# Fan_Relay.net
KiCad netlist of a schematic drawn in Altium Designer
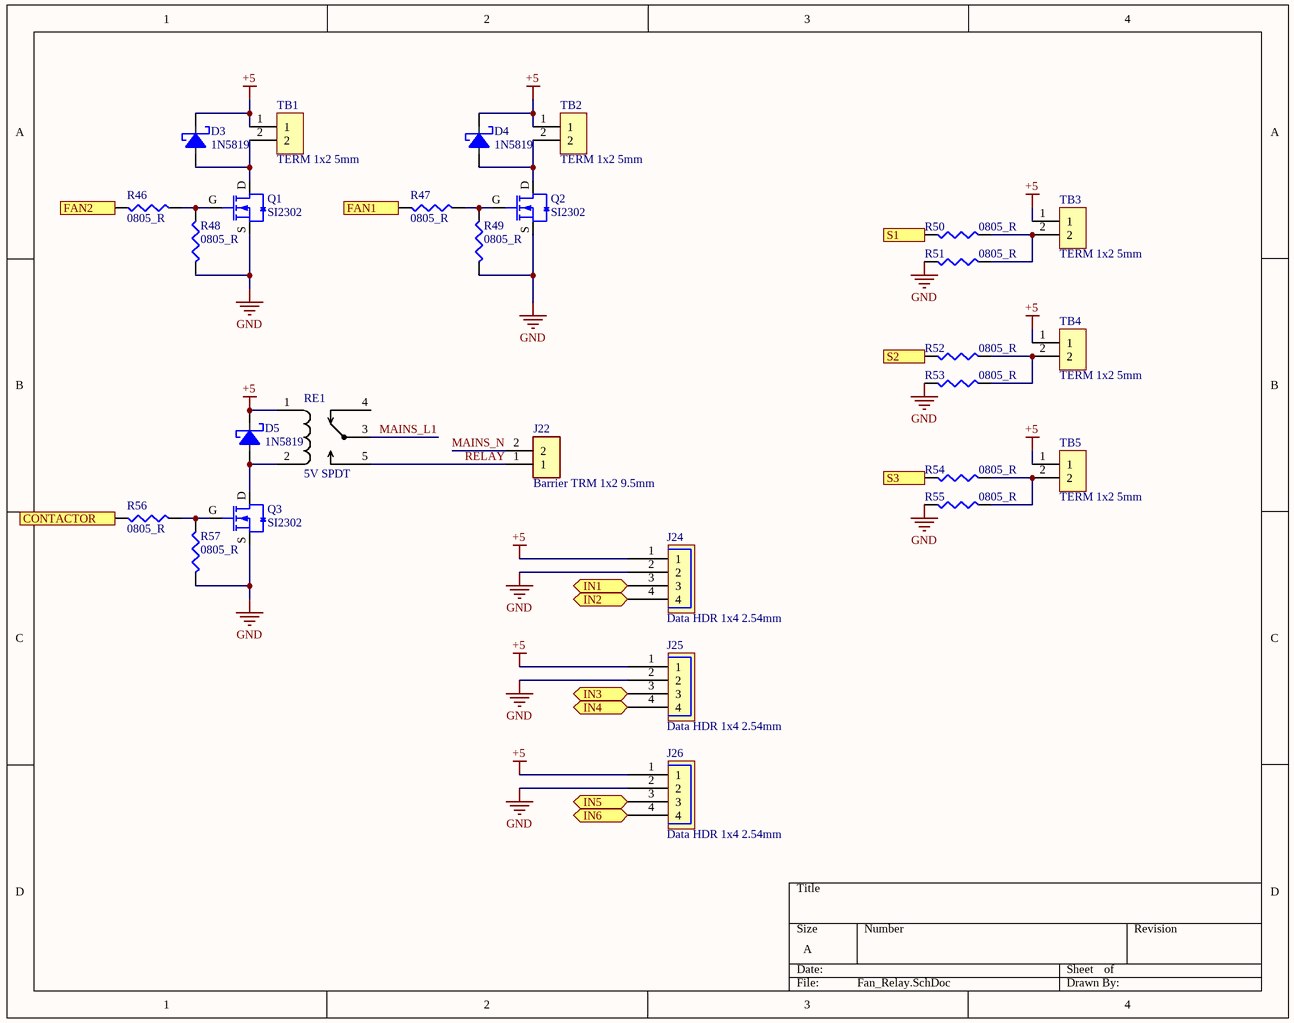
[diagram p0: Fan_Relay.SchDoc]

(export (version "E")
  (design (tool "Eeschema 10.0.6"))
  (components
    (comp (ref "D3")
      (value "1N5819")
      (footprint "D0-214AC")
      (description "1N5819 SS14 SMA Schottky Barrier Diodes (SBD) 40V 550mV@1A 1A")
      (libsource (lib "TimerSMD_Components") (part "1N5819"))
    )
    (comp (ref "D4")
      (value "1N5819")
      (footprint "D0-214AC")
      (description "1N5819 SS14 SMA Schottky Barrier Diodes (SBD) 40V 550mV@1A 1A")
      (libsource (lib "TimerSMD_Components") (part "1N5819"))
    )
    (comp (ref "D5")
      (value "1N5819")
      (footprint "D0-214AC")
      (description "1N5819 SS14 SMA Schottky Barrier Diodes (SBD) 40V 550mV@1A 1A")
      (libsource (lib "TimerSMD_Components") (part "1N5819"))
    )
    (comp (ref "J22")
      (value "Barrier TRM 1x2 9.5mm")
      (footprint "BARRIER_9.5MM")
      (description "CONN BARRIER STRIP 2CIRC 0.374\"")
      (libsource (lib "CAD_Symbols") (part "Barrier BLK"))
    )
    (comp (ref "J24")
      (value "Data HDR 1x4 2.54mm")
      (footprint "DHDR_1x4_2.54mm")
      (description "MTA-100 Series, 2.54mm Pitch 4 Way 1 RowStraight PCB Header, Solder Term, 5A")
      (libsource (lib "CAD_Symbols") (part "4-Pin Data Connector"))
    )
    (comp (ref "J25")
      (value "Data HDR 1x4 2.54mm")
      (footprint "DHDR_1x4_2.54mm")
      (description "MTA-100 Series, 2.54mm Pitch 4 Way 1 RowStraight PCB Header, Solder Term, 5A")
      (libsource (lib "CAD_Symbols") (part "4-Pin Data Connector"))
    )
    (comp (ref "J26")
      (value "Data HDR 1x4 2.54mm")
      (footprint "DHDR_1x4_2.54mm")
      (description "MTA-100 Series, 2.54mm Pitch 4 Way 1 RowStraight PCB Header, Solder Term, 5A")
      (libsource (lib "CAD_Symbols") (part "4-Pin Data Connector"))
    )
    (comp (ref "Q1")
      (value "SI2302")
      (footprint "SO-23 - MOSFET")
      (description "SI2302 A2SHB 20V 2.5A 0.9W 40mΩ@4.5V,2.5A N Channel SOT-23 MOSFET SMD")
      (libsource (lib "TimerSMD_Components") (part "SI2302"))
    )
    (comp (ref "Q2")
      (value "SI2302")
      (footprint "SO-23 - MOSFET")
      (description "SI2302 A2SHB 20V 2.5A 0.9W 40mΩ@4.5V,2.5A N Channel SOT-23 MOSFET SMD")
      (libsource (lib "TimerSMD_Components") (part "SI2302"))
    )
    (comp (ref "Q3")
      (value "SI2302")
      (footprint "SO-23 - MOSFET")
      (description "SI2302 A2SHB 20V 2.5A 0.9W 40mΩ@4.5V,2.5A N Channel SOT-23 MOSFET SMD")
      (libsource (lib "TimerSMD_Components") (part "SI2302"))
    )
    (comp (ref "R46")
      (value "0805_R")
      (footprint "R0805")
      (libsource (lib "TimerSMD_Components") (part "0805 Resistor"))
    )
    (comp (ref "R47")
      (value "0805_R")
      (footprint "R0805")
      (libsource (lib "TimerSMD_Components") (part "0805 Resistor"))
    )
    (comp (ref "R48")
      (value "0805_R")
      (footprint "R0805")
      (libsource (lib "TimerSMD_Components") (part "0805 Resistor"))
    )
    (comp (ref "R49")
      (value "0805_R")
      (footprint "R0805")
      (libsource (lib "TimerSMD_Components") (part "0805 Resistor"))
    )
    (comp (ref "R50")
      (value "0805_R")
      (footprint "R0805")
      (libsource (lib "TimerSMD_Components") (part "0805 Resistor"))
    )
    (comp (ref "R51")
      (value "0805_R")
      (footprint "R0805")
      (libsource (lib "TimerSMD_Components") (part "0805 Resistor"))
    )
    (comp (ref "R52")
      (value "0805_R")
      (footprint "R0805")
      (libsource (lib "TimerSMD_Components") (part "0805 Resistor"))
    )
    (comp (ref "R53")
      (value "0805_R")
      (footprint "R0805")
      (libsource (lib "TimerSMD_Components") (part "0805 Resistor"))
    )
    (comp (ref "R54")
      (value "0805_R")
      (footprint "R0805")
      (libsource (lib "TimerSMD_Components") (part "0805 Resistor"))
    )
    (comp (ref "R55")
      (value "0805_R")
      (footprint "R0805")
      (libsource (lib "TimerSMD_Components") (part "0805 Resistor"))
    )
    (comp (ref "R56")
      (value "0805_R")
      (footprint "R0805")
      (libsource (lib "TimerSMD_Components") (part "0805 Resistor"))
    )
    (comp (ref "R57")
      (value "0805_R")
      (footprint "R0805")
      (libsource (lib "TimerSMD_Components") (part "0805 Resistor"))
    )
    (comp (ref "RE1")
      (value "5V SPDT")
      (footprint "12mm_relay_spdt")
      (libsource (lib "EV_Symbols") (part "5V Relay"))
    )
    (comp (ref "TB1")
      (value "TERM 1x2 5mm")
      (footprint "Terminal_5mm")
      (fields (field (name "VOLTAGE") "300V"))
      (libsource (lib "CAD_Symbols") (part "Terminal BLK Green"))
    )
    (comp (ref "TB2")
      (value "TERM 1x2 5mm")
      (footprint "Terminal_5mm")
      (fields (field (name "VOLTAGE") "300V"))
      (libsource (lib "CAD_Symbols") (part "Terminal BLK Green"))
    )
    (comp (ref "TB3")
      (value "TERM 1x2 5mm")
      (footprint "Terminal_5mm")
      (fields (field (name "VOLTAGE") "300V"))
      (libsource (lib "CAD_Symbols") (part "Terminal BLK Green"))
    )
    (comp (ref "TB4")
      (value "TERM 1x2 5mm")
      (footprint "Terminal_5mm")
      (fields (field (name "VOLTAGE") "300V"))
      (libsource (lib "CAD_Symbols") (part "Terminal BLK Green"))
    )
    (comp (ref "TB5")
      (value "TERM 1x2 5mm")
      (footprint "Terminal_5mm")
      (fields (field (name "VOLTAGE") "300V"))
      (libsource (lib "CAD_Symbols") (part "Terminal BLK Green"))
    )
  )
  (nets
    (net (code "1") (name "+5") (class "Default")
      (node (ref "D3") (pin "K") (pinfunction "Cathode_K") (pintype "passive"))
      (node (ref "D4") (pin "K") (pinfunction "Cathode_K") (pintype "passive"))
      (node (ref "D5") (pin "K") (pinfunction "Cathode_K") (pintype "passive"))
      (node (ref "J24") (pin "1") (pinfunction "1_1") (pintype "passive"))
      (node (ref "J25") (pin "1") (pinfunction "1_1") (pintype "passive"))
      (node (ref "J26") (pin "1") (pinfunction "1_1") (pintype "passive"))
      (node (ref "RE1") (pin "1") (pinfunction "1_1") (pintype "passive"))
      (node (ref "TB1") (pin "1") (pinfunction "1_1") (pintype "passive"))
      (node (ref "TB2") (pin "1") (pinfunction "1_1") (pintype "passive"))
      (node (ref "TB3") (pin "1") (pinfunction "1_1") (pintype "passive"))
      (node (ref "TB4") (pin "1") (pinfunction "1_1") (pintype "passive"))
      (node (ref "TB5") (pin "1") (pinfunction "1_1") (pintype "passive"))
    )
    (net (code "2") (name "/CONTACTOR") (class "Default")
      (node (ref "R56") (pin "1") (pinfunction "1_1") (pintype "passive"))
    )
    (net (code "3") (name "/FAN1") (class "Default")
      (node (ref "R47") (pin "1") (pinfunction "1_1") (pintype "passive"))
    )
    (net (code "4") (name "/FAN2") (class "Default")
      (node (ref "R46") (pin "1") (pinfunction "1_1") (pintype "passive"))
    )
    (net (code "5") (name "/IN1") (class "Default")
      (node (ref "J24") (pin "3") (pinfunction "3_3") (pintype "passive"))
    )
    (net (code "6") (name "/IN2") (class "Default")
      (node (ref "J24") (pin "4") (pinfunction "4_4") (pintype "passive"))
    )
    (net (code "7") (name "/IN3") (class "Default")
      (node (ref "J25") (pin "3") (pinfunction "3_3") (pintype "passive"))
    )
    (net (code "8") (name "/IN4") (class "Default")
      (node (ref "J25") (pin "4") (pinfunction "4_4") (pintype "passive"))
    )
    (net (code "9") (name "/IN5") (class "Default")
      (node (ref "J26") (pin "3") (pinfunction "3_3") (pintype "passive"))
    )
    (net (code "10") (name "/IN6") (class "Default")
      (node (ref "J26") (pin "4") (pinfunction "4_4") (pintype "passive"))
    )
    (net (code "11") (name "/MAINS_L1") (class "Default")
      (node (ref "RE1") (pin "3") (pinfunction "3_3") (pintype "passive"))
    )
    (net (code "12") (name "/MAINS_N") (class "Default")
      (node (ref "J22") (pin "2") (pinfunction "2_2") (pintype "passive"))
    )
    (net (code "13") (name "/RELAY") (class "Default")
      (node (ref "J22") (pin "1") (pinfunction "1_1") (pintype "passive"))
      (node (ref "RE1") (pin "5") (pinfunction "5_5") (pintype "passive"))
    )
    (net (code "14") (name "/S1") (class "Default")
      (node (ref "R50") (pin "2") (pinfunction "2_2") (pintype "passive"))
    )
    (net (code "15") (name "/S2") (class "Default")
      (node (ref "R52") (pin "2") (pinfunction "2_2") (pintype "passive"))
    )
    (net (code "16") (name "/S3") (class "Default")
      (node (ref "R54") (pin "2") (pinfunction "2_2") (pintype "passive"))
    )
    (net (code "17") (name "GND") (class "Default")
      (node (ref "J24") (pin "2") (pinfunction "2_2") (pintype "passive"))
      (node (ref "J25") (pin "2") (pinfunction "2_2") (pintype "passive"))
      (node (ref "J26") (pin "2") (pinfunction "2_2") (pintype "passive"))
      (node (ref "Q1") (pin "S") (pinfunction "S_S") (pintype "passive"))
      (node (ref "Q2") (pin "S") (pinfunction "S_S") (pintype "passive"))
      (node (ref "Q3") (pin "S") (pinfunction "S_S") (pintype "passive"))
      (node (ref "R48") (pin "1") (pinfunction "1_1") (pintype "passive"))
      (node (ref "R49") (pin "1") (pinfunction "1_1") (pintype "passive"))
      (node (ref "R51") (pin "2") (pinfunction "2_2") (pintype "passive"))
      (node (ref "R53") (pin "2") (pinfunction "2_2") (pintype "passive"))
      (node (ref "R55") (pin "2") (pinfunction "2_2") (pintype "passive"))
      (node (ref "R57") (pin "1") (pinfunction "1_1") (pintype "passive"))
    )
    (net (code "18") (name "Net-(D3-Anode)") (class "Default")
      (node (ref "D3") (pin "A") (pinfunction "Anode_A") (pintype "passive"))
      (node (ref "Q1") (pin "D") (pinfunction "D_D") (pintype "passive"))
      (node (ref "TB1") (pin "2") (pinfunction "2_2") (pintype "passive"))
    )
    (net (code "19") (name "Net-(D4-Anode)") (class "Default")
      (node (ref "D4") (pin "A") (pinfunction "Anode_A") (pintype "passive"))
      (node (ref "Q2") (pin "D") (pinfunction "D_D") (pintype "passive"))
      (node (ref "TB2") (pin "2") (pinfunction "2_2") (pintype "passive"))
    )
    (net (code "20") (name "Net-(D5-Anode)") (class "Default")
      (node (ref "D5") (pin "A") (pinfunction "Anode_A") (pintype "passive"))
      (node (ref "Q3") (pin "D") (pinfunction "D_D") (pintype "passive"))
      (node (ref "RE1") (pin "2") (pinfunction "2_2") (pintype "passive"))
    )
    (net (code "21") (name "Net-(Q1-PadG)") (class "Default")
      (node (ref "Q1") (pin "G") (pinfunction "G_G") (pintype "passive"))
      (node (ref "R46") (pin "2") (pinfunction "2_2") (pintype "passive"))
      (node (ref "R48") (pin "2") (pinfunction "2_2") (pintype "passive"))
    )
    (net (code "22") (name "Net-(Q2-PadG)") (class "Default")
      (node (ref "Q2") (pin "G") (pinfunction "G_G") (pintype "passive"))
      (node (ref "R47") (pin "2") (pinfunction "2_2") (pintype "passive"))
      (node (ref "R49") (pin "2") (pinfunction "2_2") (pintype "passive"))
    )
    (net (code "23") (name "Net-(Q3-PadG)") (class "Default")
      (node (ref "Q3") (pin "G") (pinfunction "G_G") (pintype "passive"))
      (node (ref "R56") (pin "2") (pinfunction "2_2") (pintype "passive"))
      (node (ref "R57") (pin "2") (pinfunction "2_2") (pintype "passive"))
    )
    (net (code "24") (name "Net-(R50-Pad1)") (class "Default")
      (node (ref "R50") (pin "1") (pinfunction "1_1") (pintype "passive"))
      (node (ref "R51") (pin "1") (pinfunction "1_1") (pintype "passive"))
      (node (ref "TB3") (pin "2") (pinfunction "2_2") (pintype "passive"))
    )
    (net (code "25") (name "Net-(R52-Pad1)") (class "Default")
      (node (ref "R52") (pin "1") (pinfunction "1_1") (pintype "passive"))
      (node (ref "R53") (pin "1") (pinfunction "1_1") (pintype "passive"))
      (node (ref "TB4") (pin "2") (pinfunction "2_2") (pintype "passive"))
    )
    (net (code "26") (name "Net-(R54-Pad1)") (class "Default")
      (node (ref "R54") (pin "1") (pinfunction "1_1") (pintype "passive"))
      (node (ref "R55") (pin "1") (pinfunction "1_1") (pintype "passive"))
      (node (ref "TB5") (pin "2") (pinfunction "2_2") (pintype "passive"))
    )
    (net (code "27") (name "unconnected-(RE1-Pad4)") (class "Default")
      (node (ref "RE1") (pin "4") (pinfunction "4_4") (pintype "passive"))
    )
  )
)
